# SCH_led_esp32_2026-04-28.net
KiCad netlist of a schematic drawn in EasyEDA
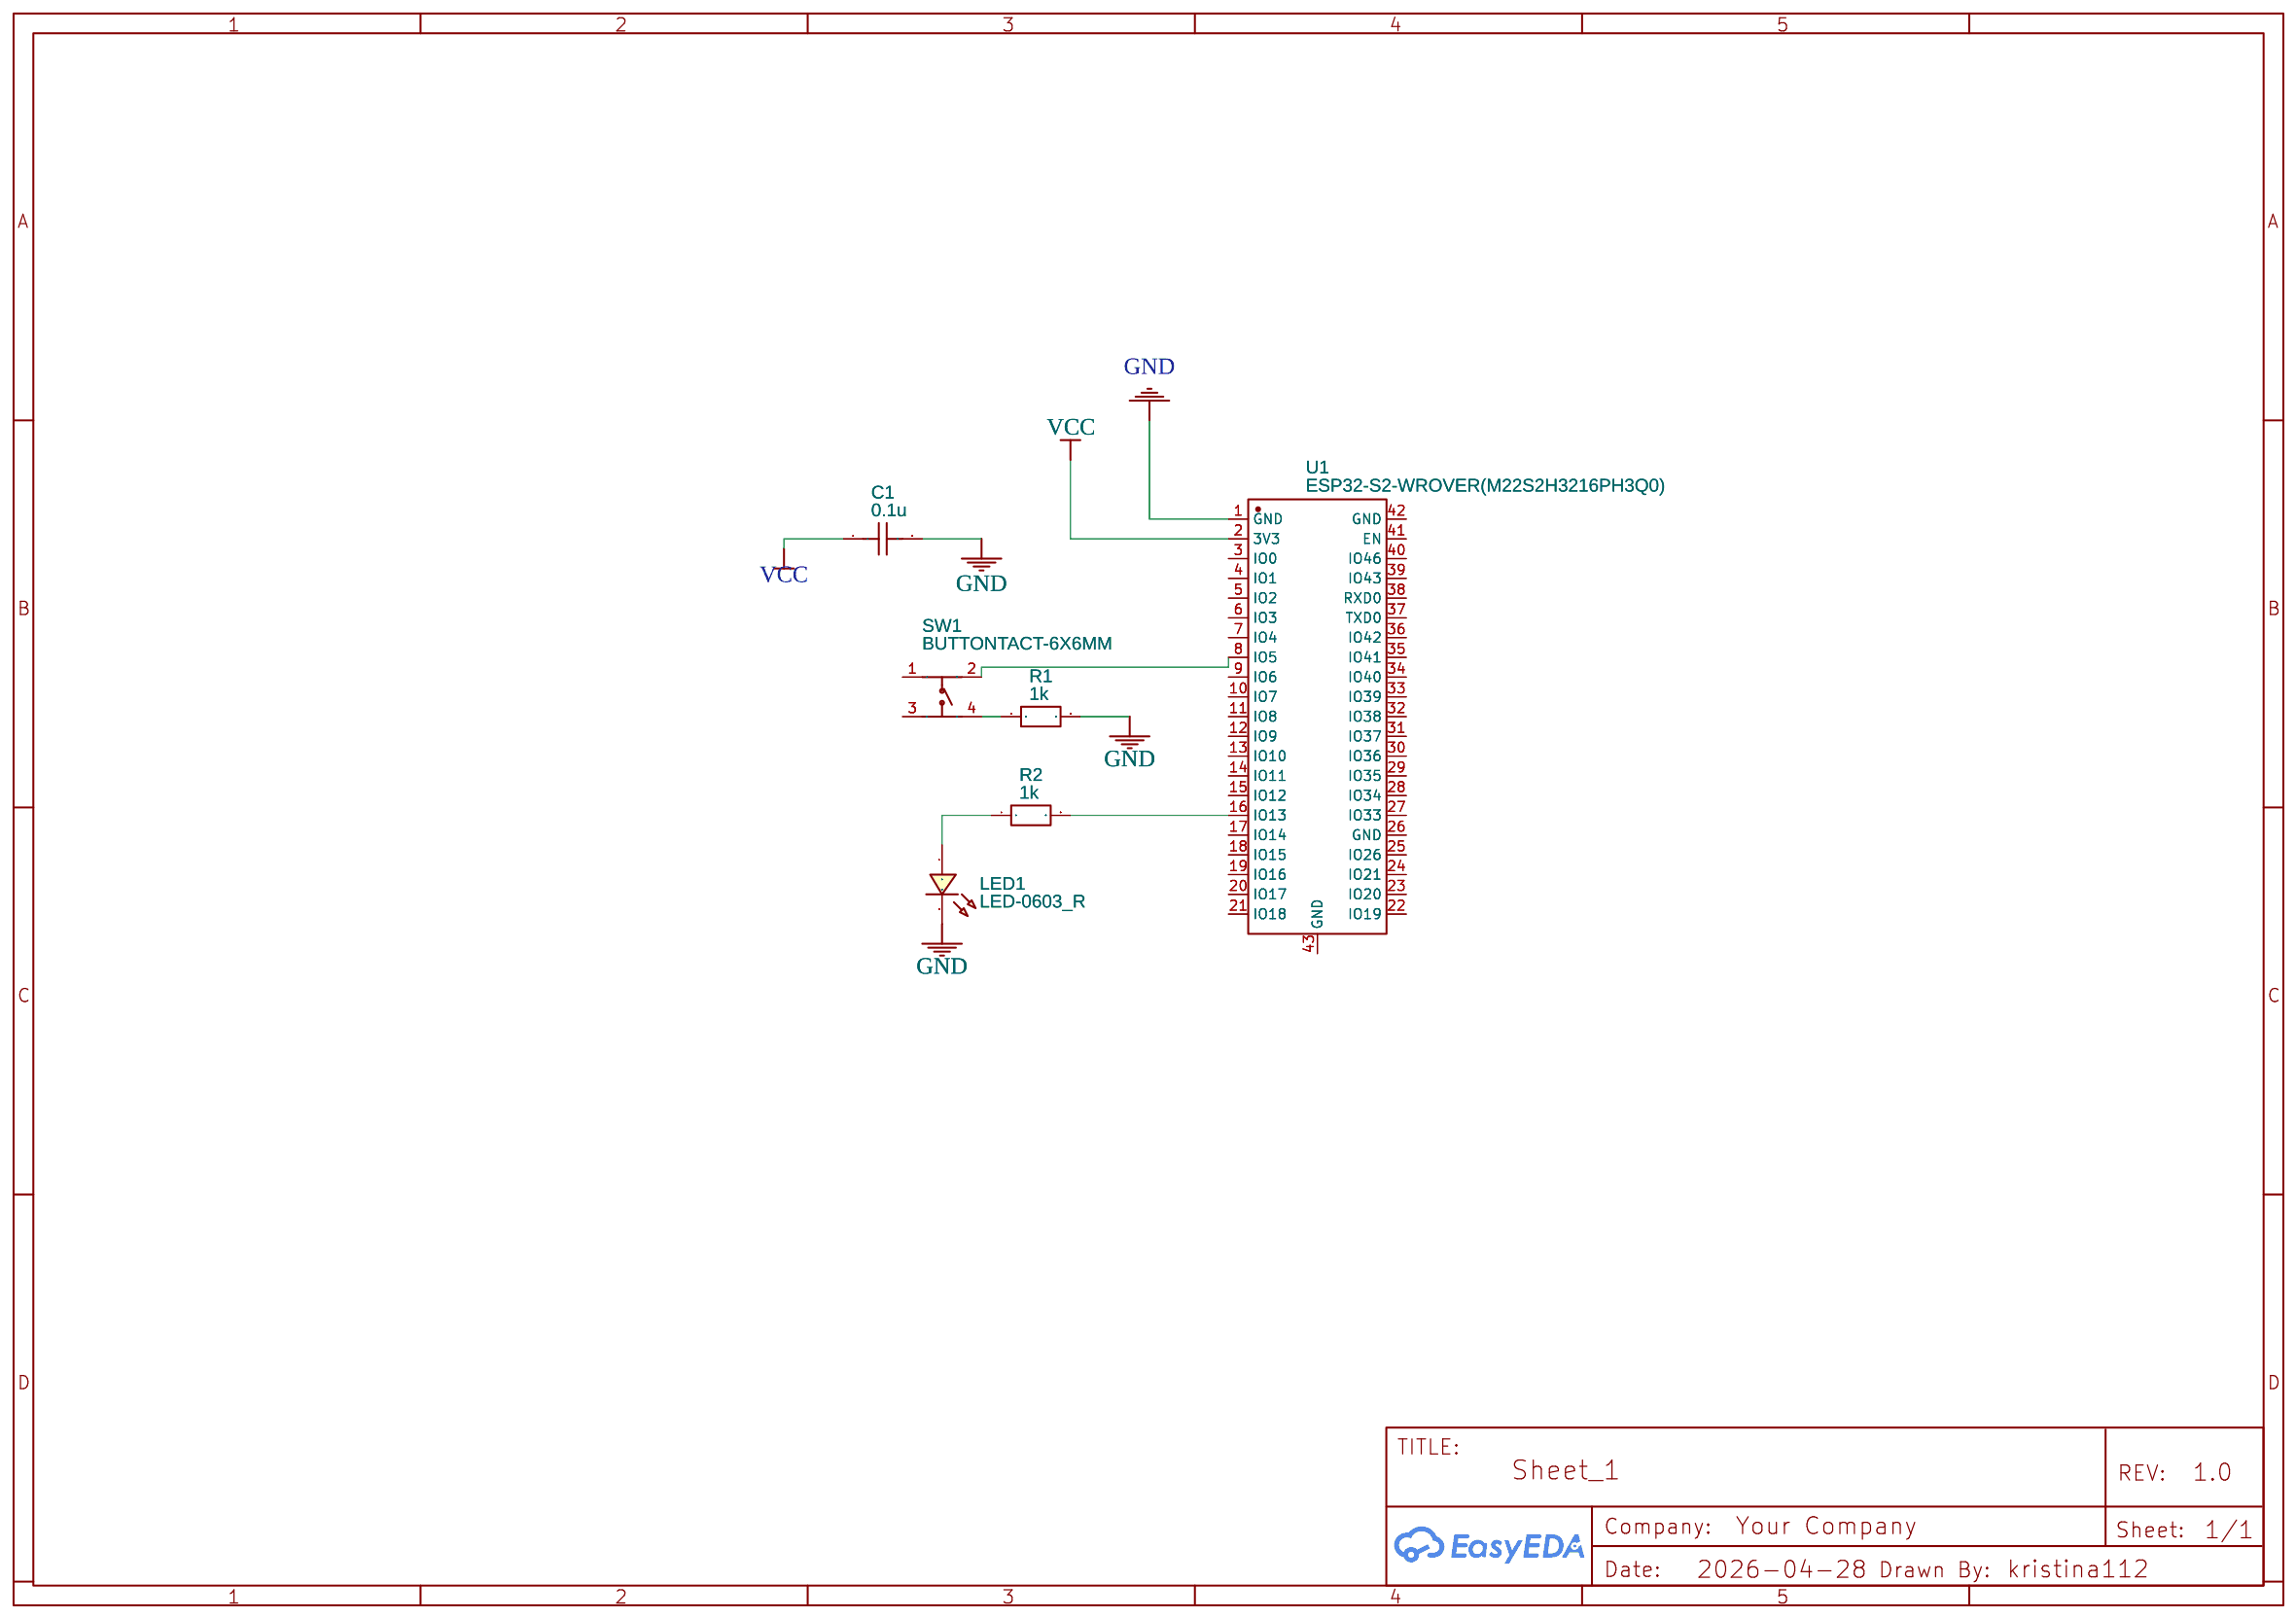
[diagram p0: schematic sheet]

(export (version "E")
  (design (tool "Eeschema 10.0.6"))
  (components
    (comp (ref "C1") (value "0.1u") (libsource (lib "") (part "C_0603_US")))
    (comp (ref "LED1")
      (value "LED-0603_R")
      (fields
        (field (name "Manufacturer Part") "19-217/R6C-AL1M2VY/3T")
        (field (name "Manufacturer") "EVERLIGHT(台湾亿光)")
      )
      (libsource (lib "") (part "LED-0603_R"))
    )
    (comp (ref "R1") (value "1k") (libsource (lib "") (part "R_0603_EU")))
    (comp (ref "R2") (value "1k") (libsource (lib "") (part "R_0603_EU")))
    (comp (ref "SW1")
      (value "BUTTONTACT-6X6MM")
      (fields (field (name "Manufacturer Part") "Buttontact-6x6mm"))
      (libsource (lib "") (part "BUTTONTACT-6X6MM"))
    )
    (comp (ref "U1")
      (value "ESP32-S2-WROVER(M22S2H3216PH3Q0)")
      (fields (field (name "Manufacturer") "ESPRESSIF(乐鑫)"))
      (libsource (lib "") (part "ESP32-S2-WROVER(M22S2H3216PH3Q0)"))
    )
  )
  (nets
    (net (code "1") (name "GND") (class "Default")
      (node (ref "C1") (pin "2") (pinfunction "2_2") (pintype "unspecified"))
      (node (ref "LED1") (pin "2") (pinfunction "2_2") (pintype "unspecified"))
      (node (ref "R1") (pin "2") (pinfunction "2_2") (pintype "unspecified"))
      (node (ref "U1") (pin "1") (pinfunction "GND_1") (pintype "unspecified"))
    )
    (net (code "2") (name "Net-(LED1-Pad1)") (class "Default")
      (node (ref "LED1") (pin "1") (pinfunction "1_1") (pintype "unspecified"))
      (node (ref "R2") (pin "1") (pinfunction "1_1") (pintype "unspecified"))
    )
    (net (code "3") (name "Net-(SW1-B)") (class "Default")
      (node (ref "SW1") (pin "2") (pinfunction "B_2") (pintype "unspecified"))
      (node (ref "U1") (pin "8") (pinfunction "IO5_8") (pintype "unspecified"))
    )
    (net (code "4") (name "Net-(SW1-D)") (class "Default")
      (node (ref "R1") (pin "1") (pinfunction "1_1") (pintype "unspecified"))
      (node (ref "SW1") (pin "4") (pinfunction "D_4") (pintype "unspecified"))
    )
    (net (code "5") (name "Net-(U1-IO13)") (class "Default")
      (node (ref "R2") (pin "2") (pinfunction "2_2") (pintype "unspecified"))
      (node (ref "U1") (pin "16") (pinfunction "IO13_16") (pintype "unspecified"))
    )
    (net (code "6") (name "VCC") (class "Default")
      (node (ref "C1") (pin "1") (pinfunction "1_1") (pintype "unspecified"))
      (node (ref "U1") (pin "2") (pinfunction "3V3_2") (pintype "unspecified"))
    )
    (net (code "7") (name "unconnected-(SW1-A-Pad1)") (class "Default")
      (node (ref "SW1") (pin "1") (pinfunction "A_1") (pintype "unspecified"))
    )
    (net (code "8") (name "unconnected-(SW1-C-Pad3)") (class "Default")
      (node (ref "SW1") (pin "3") (pinfunction "C_3") (pintype "unspecified"))
    )
    (net (code "9") (name "unconnected-(U1-EN-Pad41)") (class "Default")
      (node (ref "U1") (pin "41") (pinfunction "EN_41") (pintype "unspecified"))
    )
    (net (code "10") (name "unconnected-(U1-GND-Pad26)") (class "Default")
      (node (ref "U1") (pin "26") (pinfunction "GND_26") (pintype "unspecified"))
    )
    (net (code "11") (name "unconnected-(U1-GND-Pad42)") (class "Default")
      (node (ref "U1") (pin "42") (pinfunction "GND_42") (pintype "unspecified"))
    )
    (net (code "12") (name "unconnected-(U1-GND-Pad43)") (class "Default")
      (node (ref "U1") (pin "43") (pinfunction "GND_43") (pintype "unspecified"))
    )
    (net (code "13") (name "unconnected-(U1-IO0-Pad3)") (class "Default")
      (node (ref "U1") (pin "3") (pinfunction "IO0_3") (pintype "unspecified"))
    )
    (net (code "14") (name "unconnected-(U1-IO1-Pad4)") (class "Default")
      (node (ref "U1") (pin "4") (pinfunction "IO1_4") (pintype "unspecified"))
    )
    (net (code "15") (name "unconnected-(U1-IO2-Pad5)") (class "Default")
      (node (ref "U1") (pin "5") (pinfunction "IO2_5") (pintype "unspecified"))
    )
    (net (code "16") (name "unconnected-(U1-IO3-Pad6)") (class "Default")
      (node (ref "U1") (pin "6") (pinfunction "IO3_6") (pintype "unspecified"))
    )
    (net (code "17") (name "unconnected-(U1-IO4-Pad7)") (class "Default")
      (node (ref "U1") (pin "7") (pinfunction "IO4_7") (pintype "unspecified"))
    )
    (net (code "18") (name "unconnected-(U1-IO6-Pad9)") (class "Default")
      (node (ref "U1") (pin "9") (pinfunction "IO6_9") (pintype "unspecified"))
    )
    (net (code "19") (name "unconnected-(U1-IO7-Pad10)") (class "Default")
      (node (ref "U1") (pin "10") (pinfunction "IO7_10") (pintype "unspecified"))
    )
    (net (code "20") (name "unconnected-(U1-IO8-Pad11)") (class "Default")
      (node (ref "U1") (pin "11") (pinfunction "IO8_11") (pintype "unspecified"))
    )
    (net (code "21") (name "unconnected-(U1-IO9-Pad12)") (class "Default")
      (node (ref "U1") (pin "12") (pinfunction "IO9_12") (pintype "unspecified"))
    )
    (net (code "22") (name "unconnected-(U1-IO10-Pad13)") (class "Default")
      (node (ref "U1") (pin "13") (pinfunction "IO10_13") (pintype "unspecified"))
    )
    (net (code "23") (name "unconnected-(U1-IO11-Pad14)") (class "Default")
      (node (ref "U1") (pin "14") (pinfunction "IO11_14") (pintype "unspecified"))
    )
    (net (code "24") (name "unconnected-(U1-IO12-Pad15)") (class "Default")
      (node (ref "U1") (pin "15") (pinfunction "IO12_15") (pintype "unspecified"))
    )
    (net (code "25") (name "unconnected-(U1-IO14-Pad17)") (class "Default")
      (node (ref "U1") (pin "17") (pinfunction "IO14_17") (pintype "unspecified"))
    )
    (net (code "26") (name "unconnected-(U1-IO15-Pad18)") (class "Default")
      (node (ref "U1") (pin "18") (pinfunction "IO15_18") (pintype "unspecified"))
    )
    (net (code "27") (name "unconnected-(U1-IO16-Pad19)") (class "Default")
      (node (ref "U1") (pin "19") (pinfunction "IO16_19") (pintype "unspecified"))
    )
    (net (code "28") (name "unconnected-(U1-IO17-Pad20)") (class "Default")
      (node (ref "U1") (pin "20") (pinfunction "IO17_20") (pintype "unspecified"))
    )
    (net (code "29") (name "unconnected-(U1-IO18-Pad21)") (class "Default")
      (node (ref "U1") (pin "21") (pinfunction "IO18_21") (pintype "unspecified"))
    )
    (net (code "30") (name "unconnected-(U1-IO19-Pad22)") (class "Default")
      (node (ref "U1") (pin "22") (pinfunction "IO19_22") (pintype "unspecified"))
    )
    (net (code "31") (name "unconnected-(U1-IO20-Pad23)") (class "Default")
      (node (ref "U1") (pin "23") (pinfunction "IO20_23") (pintype "unspecified"))
    )
    (net (code "32") (name "unconnected-(U1-IO21-Pad24)") (class "Default")
      (node (ref "U1") (pin "24") (pinfunction "IO21_24") (pintype "unspecified"))
    )
    (net (code "33") (name "unconnected-(U1-IO26-Pad25)") (class "Default")
      (node (ref "U1") (pin "25") (pinfunction "IO26_25") (pintype "unspecified"))
    )
    (net (code "34") (name "unconnected-(U1-IO33-Pad27)") (class "Default")
      (node (ref "U1") (pin "27") (pinfunction "IO33_27") (pintype "unspecified"))
    )
    (net (code "35") (name "unconnected-(U1-IO34-Pad28)") (class "Default")
      (node (ref "U1") (pin "28") (pinfunction "IO34_28") (pintype "unspecified"))
    )
    (net (code "36") (name "unconnected-(U1-IO35-Pad29)") (class "Default")
      (node (ref "U1") (pin "29") (pinfunction "IO35_29") (pintype "unspecified"))
    )
    (net (code "37") (name "unconnected-(U1-IO36-Pad30)") (class "Default")
      (node (ref "U1") (pin "30") (pinfunction "IO36_30") (pintype "unspecified"))
    )
    (net (code "38") (name "unconnected-(U1-IO37-Pad31)") (class "Default")
      (node (ref "U1") (pin "31") (pinfunction "IO37_31") (pintype "unspecified"))
    )
    (net (code "39") (name "unconnected-(U1-IO38-Pad32)") (class "Default")
      (node (ref "U1") (pin "32") (pinfunction "IO38_32") (pintype "unspecified"))
    )
    (net (code "40") (name "unconnected-(U1-IO39-Pad33)") (class "Default")
      (node (ref "U1") (pin "33") (pinfunction "IO39_33") (pintype "unspecified"))
    )
    (net (code "41") (name "unconnected-(U1-IO40-Pad34)") (class "Default")
      (node (ref "U1") (pin "34") (pinfunction "IO40_34") (pintype "unspecified"))
    )
    (net (code "42") (name "unconnected-(U1-IO41-Pad35)") (class "Default")
      (node (ref "U1") (pin "35") (pinfunction "IO41_35") (pintype "unspecified"))
    )
    (net (code "43") (name "unconnected-(U1-IO42-Pad36)") (class "Default")
      (node (ref "U1") (pin "36") (pinfunction "IO42_36") (pintype "unspecified"))
    )
    (net (code "44") (name "unconnected-(U1-IO43-Pad39)") (class "Default")
      (node (ref "U1") (pin "39") (pinfunction "IO43_39") (pintype "unspecified"))
    )
    (net (code "45") (name "unconnected-(U1-IO46-Pad40)") (class "Default")
      (node (ref "U1") (pin "40") (pinfunction "IO46_40") (pintype "unspecified"))
    )
    (net (code "46") (name "unconnected-(U1-RXD0-Pad38)") (class "Default")
      (node (ref "U1") (pin "38") (pinfunction "RXD0_38") (pintype "unspecified"))
    )
    (net (code "47") (name "unconnected-(U1-TXD0-Pad37)") (class "Default")
      (node (ref "U1") (pin "37") (pinfunction "TXD0_37") (pintype "unspecified"))
    )
  )
)
